# AD9850.net
KiCad netlist of a schematic drawn in Altium Designer
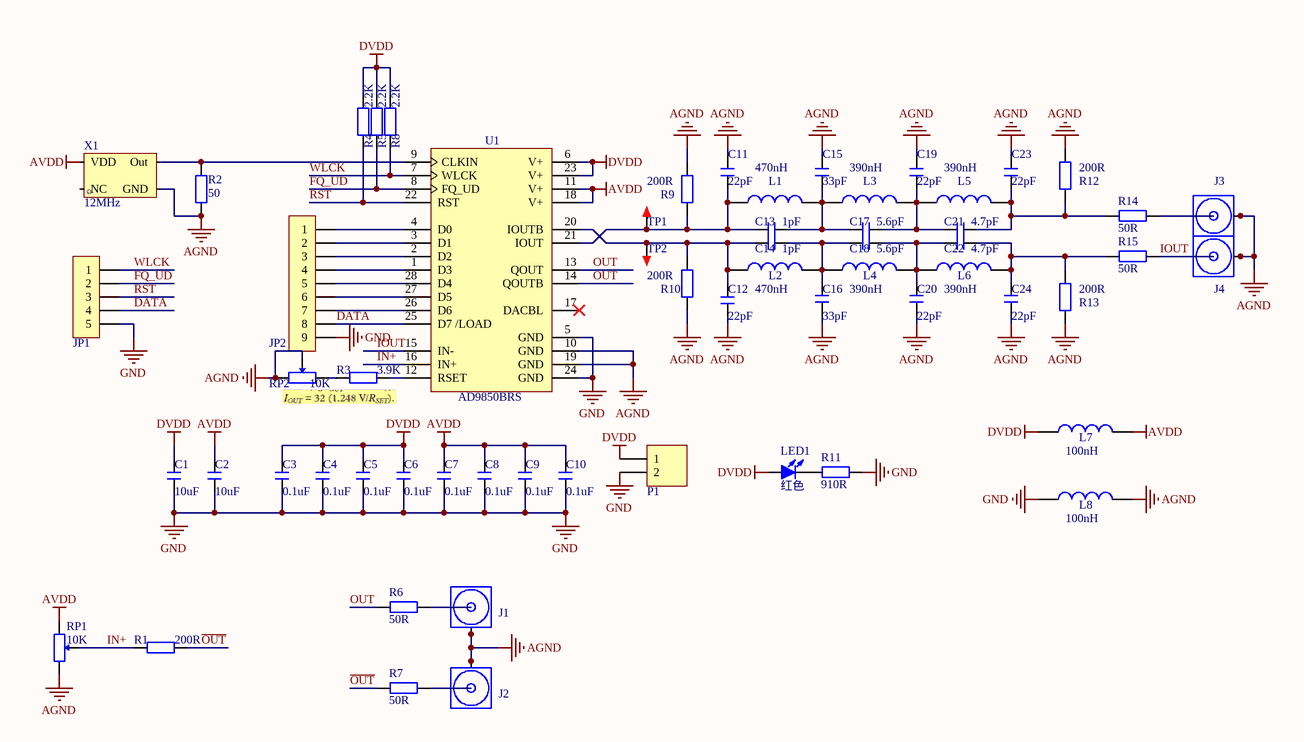
[diagram p0: AD9850模块.SchDoc]

(export (version "E")
  (design (tool "Eeschema 10.0.6"))
  (components
    (comp (ref "C1")
      (value "10uF")
      (footprint "C 0805")
      (description "无极性贴片电容")
      (fields (field (name "版权归属") "源创客"))
      (libsource (lib "电阻-电容-电感") (part "C"))
    )
    (comp (ref "C2")
      (value "10uF")
      (footprint "C 0805")
      (description "无极性贴片电容")
      (fields (field (name "版权归属") "源创客"))
      (libsource (lib "电阻-电容-电感") (part "C"))
    )
    (comp (ref "C3")
      (value "0.1uF")
      (footprint "C 0805")
      (description "无极性贴片电容")
      (fields (field (name "版权归属") "源创客"))
      (libsource (lib "电阻-电容-电感") (part "C"))
    )
    (comp (ref "C4")
      (value "0.1uF")
      (footprint "C 0805")
      (description "无极性贴片电容")
      (fields (field (name "版权归属") "源创客"))
      (libsource (lib "电阻-电容-电感") (part "C"))
    )
    (comp (ref "C5")
      (value "0.1uF")
      (footprint "C 0805")
      (description "无极性贴片电容")
      (fields (field (name "版权归属") "源创客"))
      (libsource (lib "电阻-电容-电感") (part "C"))
    )
    (comp (ref "C6")
      (value "0.1uF")
      (footprint "C 0805")
      (description "无极性贴片电容")
      (fields (field (name "版权归属") "源创客"))
      (libsource (lib "电阻-电容-电感") (part "C"))
    )
    (comp (ref "C7")
      (value "0.1uF")
      (footprint "C 0805")
      (description "无极性贴片电容")
      (fields (field (name "版权归属") "源创客"))
      (libsource (lib "电阻-电容-电感") (part "C"))
    )
    (comp (ref "C8")
      (value "0.1uF")
      (footprint "C 0805")
      (description "无极性贴片电容")
      (fields (field (name "版权归属") "源创客"))
      (libsource (lib "电阻-电容-电感") (part "C"))
    )
    (comp (ref "C9")
      (value "0.1uF")
      (footprint "C 0805")
      (description "无极性贴片电容")
      (fields (field (name "版权归属") "源创客"))
      (libsource (lib "电阻-电容-电感") (part "C"))
    )
    (comp (ref "C10")
      (value "0.1uF")
      (footprint "C 0805")
      (description "无极性贴片电容")
      (fields (field (name "版权归属") "源创客"))
      (libsource (lib "电阻-电容-电感") (part "C"))
    )
    (comp (ref "C11")
      (value "22pF")
      (footprint "C 0603")
      (description "无极性贴片电容")
      (fields (field (name "版权归属") "源创客"))
      (libsource (lib "电阻-电容-电感") (part "C"))
    )
    (comp (ref "C12")
      (value "22pF")
      (footprint "C 0603")
      (description "无极性贴片电容")
      (fields (field (name "版权归属") "源创客"))
      (libsource (lib "电阻-电容-电感") (part "C"))
    )
    (comp (ref "C13")
      (value "1pF")
      (footprint "C 0603")
      (description "无极性贴片电容")
      (fields (field (name "版权归属") "源创客"))
      (libsource (lib "电阻-电容-电感") (part "C"))
    )
    (comp (ref "C14")
      (value "1pF")
      (footprint "C 0603")
      (description "无极性贴片电容")
      (fields (field (name "版权归属") "源创客"))
      (libsource (lib "电阻-电容-电感") (part "C"))
    )
    (comp (ref "C15")
      (value "33pF")
      (footprint "C 0603")
      (description "无极性贴片电容")
      (fields (field (name "版权归属") "源创客"))
      (libsource (lib "电阻-电容-电感") (part "C"))
    )
    (comp (ref "C16")
      (value "33pF")
      (footprint "C 0603")
      (description "无极性贴片电容")
      (fields (field (name "版权归属") "源创客"))
      (libsource (lib "电阻-电容-电感") (part "C"))
    )
    (comp (ref "C17")
      (value "5.6pF")
      (footprint "C 0603")
      (description "无极性贴片电容")
      (fields (field (name "版权归属") "源创客"))
      (libsource (lib "电阻-电容-电感") (part "C"))
    )
    (comp (ref "C18")
      (value "5.6pF")
      (footprint "C 0603")
      (description "无极性贴片电容")
      (fields (field (name "版权归属") "源创客"))
      (libsource (lib "电阻-电容-电感") (part "C"))
    )
    (comp (ref "C19")
      (value "22pF")
      (footprint "C 0603")
      (description "无极性贴片电容")
      (fields (field (name "版权归属") "源创客"))
      (libsource (lib "电阻-电容-电感") (part "C"))
    )
    (comp (ref "C20")
      (value "22pF")
      (footprint "C 0603")
      (description "无极性贴片电容")
      (fields (field (name "版权归属") "源创客"))
      (libsource (lib "电阻-电容-电感") (part "C"))
    )
    (comp (ref "C21")
      (value "4.7pF")
      (footprint "C 0603")
      (description "无极性贴片电容")
      (fields (field (name "版权归属") "源创客"))
      (libsource (lib "电阻-电容-电感") (part "C"))
    )
    (comp (ref "C22")
      (value "4.7pF")
      (footprint "C 0603")
      (description "无极性贴片电容")
      (fields (field (name "版权归属") "源创客"))
      (libsource (lib "电阻-电容-电感") (part "C"))
    )
    (comp (ref "C23")
      (value "22pF")
      (footprint "C 0603")
      (description "无极性贴片电容")
      (fields (field (name "版权归属") "源创客"))
      (libsource (lib "电阻-电容-电感") (part "C"))
    )
    (comp (ref "C24")
      (value "22pF")
      (footprint "C 0603")
      (description "无极性贴片电容")
      (fields (field (name "版权归属") "源创客"))
      (libsource (lib "电阻-电容-电感") (part "C"))
    )
    (comp (ref "J1") (value "COAX") (footprint "MCX5.08-5-H") (libsource (lib "LIB") (part "COAX")))
    (comp (ref "J2") (value "COAX") (footprint "MCX5.08-5-H") (libsource (lib "LIB") (part "COAX")))
    (comp (ref "J3") (value "COAX") (footprint "MCX5.08-5-H") (libsource (lib "LIB") (part "COAX")))
    (comp (ref "J4") (value "COAX") (footprint "MCX5.08-5-H") (libsource (lib "LIB") (part "COAX")))
    (comp (ref "JP1")
      (value "HDR-1X5")
      (footprint "HDR-1X5_H")
      (description "5P接插件")
      (fields (field (name "版权归属") "源创客"))
      (libsource (lib "接插件") (part "Header 5"))
    )
    (comp (ref "JP2")
      (value "HDR-1X9")
      (footprint "HDR-1X9_H")
      (description "9P接插件")
      (fields (field (name "版权归属") "源创客"))
      (libsource (lib "接插件") (part "Header 9"))
    )
    (comp (ref "L1")
      (value "470nH")
      (footprint "L 0603")
      (description "小功率贴片电感")
      (fields (field (name "版权归属") "源创客"))
      (libsource (lib "电阻-电容-电感") (part "L"))
    )
    (comp (ref "L2")
      (value "470nH")
      (footprint "L 0603")
      (description "小功率贴片电感")
      (fields (field (name "版权归属") "源创客"))
      (libsource (lib "电阻-电容-电感") (part "L"))
    )
    (comp (ref "L3")
      (value "390nH")
      (footprint "L 0603")
      (description "小功率贴片电感")
      (fields (field (name "版权归属") "源创客"))
      (libsource (lib "电阻-电容-电感") (part "L"))
    )
    (comp (ref "L4")
      (value "390nH")
      (footprint "L 0603")
      (description "小功率贴片电感")
      (fields (field (name "版权归属") "源创客"))
      (libsource (lib "电阻-电容-电感") (part "L"))
    )
    (comp (ref "L5")
      (value "390nH")
      (footprint "L 0603")
      (description "小功率贴片电感")
      (fields (field (name "版权归属") "源创客"))
      (libsource (lib "电阻-电容-电感") (part "L"))
    )
    (comp (ref "L6")
      (value "390nH")
      (footprint "L 0603")
      (description "小功率贴片电感")
      (fields (field (name "版权归属") "源创客"))
      (libsource (lib "电阻-电容-电感") (part "L"))
    )
    (comp (ref "L7")
      (value "100nH")
      (footprint "L 0603")
      (description "小功率贴片电感")
      (fields (field (name "版权归属") "源创客"))
      (libsource (lib "电阻-电容-电感") (part "L"))
    )
    (comp (ref "L8")
      (value "100nH")
      (footprint "L 0603")
      (description "小功率贴片电感")
      (fields (field (name "版权归属") "源创客"))
      (libsource (lib "电阻-电容-电感") (part "L"))
    )
    (comp (ref "LED1")
      (value "红色")
      (footprint "LED 0805G")
      (description "贴片LED")
      (fields (field (name "版权归属") "源创客"))
      (libsource (lib "LED") (part "LED-SMD"))
    )
    (comp (ref "P1")
      (value "Header 2")
      (footprint "HDR2X1_B2")
      (description "接插件")
      (fields (field (name "PUBLISHER") "Altium Limited"))
      (libsource (lib "LIB") (part "Header 2"))
    )
    (comp (ref "R1")
      (value "200R")
      (footprint "R 0603")
      (description "贴片电阻")
      (fields (field (name "版权归属") "源创客"))
      (libsource (lib "电阻-电容-电感") (part "R"))
    )
    (comp (ref "R2")
      (value "50")
      (footprint "R 0603")
      (description "贴片电阻")
      (fields (field (name "版权归属") "源创客"))
      (libsource (lib "电阻-电容-电感") (part "R"))
    )
    (comp (ref "R3")
      (value "3.9K")
      (footprint "R 0603")
      (description "贴片电阻")
      (fields (field (name "版权归属") "源创客"))
      (libsource (lib "电阻-电容-电感") (part "R"))
    )
    (comp (ref "R4")
      (value "2.2K")
      (footprint "R 0805")
      (description "贴片电阻")
      (fields (field (name "版权归属") "源创客"))
      (libsource (lib "电阻-电容-电感") (part "R"))
    )
    (comp (ref "R5")
      (value "2.2K")
      (footprint "R 0805")
      (description "贴片电阻")
      (fields (field (name "版权归属") "源创客"))
      (libsource (lib "电阻-电容-电感") (part "R"))
    )
    (comp (ref "R6")
      (value "50R")
      (footprint "R 0603")
      (description "贴片电阻")
      (fields (field (name "版权归属") "源创客"))
      (libsource (lib "电阻-电容-电感") (part "R"))
    )
    (comp (ref "R7")
      (value "50R")
      (footprint "R 0603")
      (description "贴片电阻")
      (fields (field (name "版权归属") "源创客"))
      (libsource (lib "电阻-电容-电感") (part "R"))
    )
    (comp (ref "R8")
      (value "2.2K")
      (footprint "R 0805")
      (description "贴片电阻")
      (fields (field (name "版权归属") "源创客"))
      (libsource (lib "电阻-电容-电感") (part "R"))
    )
    (comp (ref "R9")
      (value "200R")
      (footprint "R 0603")
      (description "贴片电阻")
      (fields (field (name "版权归属") "源创客"))
      (libsource (lib "电阻-电容-电感") (part "R"))
    )
    (comp (ref "R10")
      (value "200R")
      (footprint "R 0603")
      (description "贴片电阻")
      (fields (field (name "版权归属") "源创客"))
      (libsource (lib "电阻-电容-电感") (part "R"))
    )
    (comp (ref "R11")
      (value "910R")
      (footprint "R 0805")
      (description "贴片电阻")
      (fields (field (name "版权归属") "源创客"))
      (libsource (lib "电阻-电容-电感") (part "R"))
    )
    (comp (ref "R12")
      (value "200R")
      (footprint "R 0603")
      (description "贴片电阻")
      (fields (field (name "版权归属") "源创客"))
      (libsource (lib "电阻-电容-电感") (part "R"))
    )
    (comp (ref "R13")
      (value "200R")
      (footprint "R 0603")
      (description "贴片电阻")
      (fields (field (name "版权归属") "源创客"))
      (libsource (lib "电阻-电容-电感") (part "R"))
    )
    (comp (ref "R14")
      (value "50R")
      (footprint "R 0603")
      (description "贴片电阻")
      (fields (field (name "版权归属") "源创客"))
      (libsource (lib "电阻-电容-电感") (part "R"))
    )
    (comp (ref "R15")
      (value "50R")
      (footprint "R 0603")
      (description "贴片电阻")
      (fields (field (name "版权归属") "源创客"))
      (libsource (lib "电阻-电容-电感") (part "R"))
    )
    (comp (ref "RP1")
      (value "10K")
      (footprint "3296W")
      (description "插件单联电位器")
      (fields (field (name "版权归属") "源创客"))
      (libsource (lib "电阻-电容-电感") (part "RP-ID"))
    )
    (comp (ref "RP2")
      (value "10K")
      (footprint "3296W")
      (description "插件单联电位器")
      (fields (field (name "版权归属") "源创客"))
      (libsource (lib "电阻-电容-电感") (part "RP-ID"))
    )
    (comp (ref "TP1")
      (value "TEST TP")
      (footprint "TEST TP1.4_B")
      (description "测试环")
      (fields (field (name "版权归属") "源创客"))
      (libsource (lib "未分类器件") (part "TEST TP"))
    )
    (comp (ref "TP2")
      (value "TEST TP")
      (footprint "TEST TP1.4_B")
      (description "测试环")
      (fields (field (name "版权归属") "源创客"))
      (libsource (lib "未分类器件") (part "TEST TP"))
    )
    (comp (ref "U1")
      (value "AD9850BRS")
      (footprint "RS-28")
      (description "CMOS, 125MHz Complete DDS Synthesizer")
      (fields (field (name "PUBLISHER") "Altium Limited"))
      (libsource (lib "AD RF and IF Frequency Synthesiser") (part "AD9850BRS"))
    )
    (comp (ref "X1")
      (value "XTAL")
      (footprint "X-CPX75")
      (description "有源晶振")
      (fields (field (name "FREQUENCY") "12MHz"))
      (libsource (lib "LIB") (part "XTAL_Oscillator"))
    )
  )
  (nets
    (net (code "1") (name "/DATA") (class "Default")
      (node (ref "JP1") (pin "4") (pinfunction "4_4") (pintype "passive"))
      (node (ref "JP2") (pin "8") (pinfunction "8_8") (pintype "passive"))
      (node (ref "U1") (pin "25") (pinfunction "D7_/LOAD_25") (pintype "passive"))
    )
    (net (code "2") (name "/FQ_UD") (class "Default")
      (node (ref "JP1") (pin "2") (pinfunction "2_2") (pintype "passive"))
      (node (ref "R5") (pin "1") (pinfunction "1_1") (pintype "passive"))
      (node (ref "U1") (pin "8") (pinfunction "FQ_UD_8") (pintype "passive"))
    )
    (net (code "3") (name "/IN+") (class "Default")
      (node (ref "R1") (pin "2") (pinfunction "2_2") (pintype "passive"))
      (node (ref "RP1") (pin "2") (pinfunction "2_2") (pintype "passive"))
      (node (ref "U1") (pin "16") (pinfunction "IN+_16") (pintype "passive"))
    )
    (net (code "4") (name "/IOUT") (class "Default")
      (node (ref "J4") (pin "1") (pinfunction "Signal_1") (pintype "passive"))
      (node (ref "R15") (pin "1") (pinfunction "1_1") (pintype "passive"))
      (node (ref "U1") (pin "15") (pinfunction "IN-_15") (pintype "passive"))
    )
    (net (code "5") (name "/OUT") (class "Default")
      (node (ref "R6") (pin "2") (pinfunction "2_2") (pintype "passive"))
      (node (ref "U1") (pin "13") (pinfunction "QOUT_13") (pintype "passive"))
    )
    (net (code "6") (name "/RST") (class "Default")
      (node (ref "JP1") (pin "3") (pinfunction "3_3") (pintype "passive"))
      (node (ref "R4") (pin "1") (pinfunction "1_1") (pintype "passive"))
      (node (ref "U1") (pin "22") (pinfunction "RST_22") (pintype "passive"))
    )
    (net (code "7") (name "/WLCK") (class "Default")
      (node (ref "JP1") (pin "1") (pinfunction "1_1") (pintype "passive"))
      (node (ref "R8") (pin "1") (pinfunction "1_1") (pintype "passive"))
      (node (ref "U1") (pin "7") (pinfunction "WLCK_7") (pintype "passive"))
    )
    (net (code "8") (name "/~{OUT}") (class "Default")
      (node (ref "R1") (pin "1") (pinfunction "1_1") (pintype "passive"))
      (node (ref "R7") (pin "2") (pinfunction "2_2") (pintype "passive"))
      (node (ref "U1") (pin "14") (pinfunction "QOUTB_14") (pintype "passive"))
    )
    (net (code "9") (name "AGND") (class "Default")
      (node (ref "C11") (pin "2") (pinfunction "2_2") (pintype "passive"))
      (node (ref "C12") (pin "2") (pinfunction "2_2") (pintype "passive"))
      (node (ref "C15") (pin "2") (pinfunction "2_2") (pintype "passive"))
      (node (ref "C16") (pin "2") (pinfunction "2_2") (pintype "passive"))
      (node (ref "C19") (pin "2") (pinfunction "2_2") (pintype "passive"))
      (node (ref "C20") (pin "2") (pinfunction "2_2") (pintype "passive"))
      (node (ref "C23") (pin "2") (pinfunction "2_2") (pintype "passive"))
      (node (ref "C24") (pin "2") (pinfunction "2_2") (pintype "passive"))
      (node (ref "J1") (pin "2") (pinfunction "GND_2") (pintype "passive"))
      (node (ref "J1") (pin "3") (pinfunction "GND_3") (pintype "passive"))
      (node (ref "J1") (pin "4") (pinfunction "GND_4") (pintype "passive"))
      (node (ref "J1") (pin "5") (pinfunction "GND_5") (pintype "passive"))
      (node (ref "J2") (pin "2") (pinfunction "GND_2") (pintype "passive"))
      (node (ref "J2") (pin "3") (pinfunction "GND_3") (pintype "passive"))
      (node (ref "J2") (pin "4") (pinfunction "GND_4") (pintype "passive"))
      (node (ref "J2") (pin "5") (pinfunction "GND_5") (pintype "passive"))
      (node (ref "J3") (pin "2") (pinfunction "GND_2") (pintype "passive"))
      (node (ref "J3") (pin "3") (pinfunction "GND_3") (pintype "passive"))
      (node (ref "J3") (pin "4") (pinfunction "GND_4") (pintype "passive"))
      (node (ref "J3") (pin "5") (pinfunction "GND_5") (pintype "passive"))
      (node (ref "J4") (pin "2") (pinfunction "GND_2") (pintype "passive"))
      (node (ref "J4") (pin "3") (pinfunction "GND_3") (pintype "passive"))
      (node (ref "J4") (pin "4") (pinfunction "GND_4") (pintype "passive"))
      (node (ref "J4") (pin "5") (pinfunction "GND_5") (pintype "passive"))
      (node (ref "L8") (pin "2") (pinfunction "2_2") (pintype "passive"))
      (node (ref "R10") (pin "1") (pinfunction "1_1") (pintype "passive"))
      (node (ref "R12") (pin "2") (pinfunction "2_2") (pintype "passive"))
      (node (ref "R13") (pin "1") (pinfunction "1_1") (pintype "passive"))
      (node (ref "R2") (pin "1") (pinfunction "1_1") (pintype "passive"))
      (node (ref "R9") (pin "2") (pinfunction "2_2") (pintype "passive"))
      (node (ref "RP1") (pin "3") (pinfunction "3_3") (pintype "passive"))
      (node (ref "RP2") (pin "1") (pinfunction "1_1") (pintype "passive"))
      (node (ref "RP2") (pin "2") (pinfunction "2_2") (pintype "passive"))
      (node (ref "U1") (pin "10") (pinfunction "GND_10") (pintype "power_in"))
      (node (ref "U1") (pin "19") (pinfunction "GND_19") (pintype "power_in"))
      (node (ref "X1") (pin "2") (pinfunction "GND_2") (pintype "passive"))
    )
    (net (code "10") (name "AVDD") (class "Default")
      (node (ref "C10") (pin "2") (pinfunction "2_2") (pintype "passive"))
      (node (ref "C2") (pin "2") (pinfunction "2_2") (pintype "passive"))
      (node (ref "C7") (pin "2") (pinfunction "2_2") (pintype "passive"))
      (node (ref "C8") (pin "2") (pinfunction "2_2") (pintype "passive"))
      (node (ref "C9") (pin "2") (pinfunction "2_2") (pintype "passive"))
      (node (ref "L7") (pin "2") (pinfunction "2_2") (pintype "passive"))
      (node (ref "RP1") (pin "1") (pinfunction "1_1") (pintype "passive"))
      (node (ref "U1") (pin "11") (pinfunction "V+_11") (pintype "power_in"))
      (node (ref "U1") (pin "18") (pinfunction "V+_18") (pintype "power_in"))
      (node (ref "X1") (pin "4") (pinfunction "VDD_4") (pintype "passive"))
    )
    (net (code "11") (name "DVDD") (class "Default")
      (node (ref "C1") (pin "2") (pinfunction "2_2") (pintype "passive"))
      (node (ref "C3") (pin "2") (pinfunction "2_2") (pintype "passive"))
      (node (ref "C4") (pin "2") (pinfunction "2_2") (pintype "passive"))
      (node (ref "C5") (pin "2") (pinfunction "2_2") (pintype "passive"))
      (node (ref "C6") (pin "2") (pinfunction "2_2") (pintype "passive"))
      (node (ref "L7") (pin "1") (pinfunction "1_1") (pintype "passive"))
      (node (ref "LED1") (pin "1") (pinfunction "A_1") (pintype "passive"))
      (node (ref "P1") (pin "1") (pinfunction "1_1") (pintype "passive"))
      (node (ref "R4") (pin "2") (pinfunction "2_2") (pintype "passive"))
      (node (ref "R5") (pin "2") (pinfunction "2_2") (pintype "passive"))
      (node (ref "R8") (pin "2") (pinfunction "2_2") (pintype "passive"))
      (node (ref "U1") (pin "23") (pinfunction "V+_23") (pintype "power_in"))
      (node (ref "U1") (pin "6") (pinfunction "V+_6") (pintype "power_in"))
    )
    (net (code "12") (name "GND") (class "Default")
      (node (ref "C1") (pin "1") (pinfunction "1_1") (pintype "passive"))
      (node (ref "C10") (pin "1") (pinfunction "1_1") (pintype "passive"))
      (node (ref "C2") (pin "1") (pinfunction "1_1") (pintype "passive"))
      (node (ref "C3") (pin "1") (pinfunction "1_1") (pintype "passive"))
      (node (ref "C4") (pin "1") (pinfunction "1_1") (pintype "passive"))
      (node (ref "C5") (pin "1") (pinfunction "1_1") (pintype "passive"))
      (node (ref "C6") (pin "1") (pinfunction "1_1") (pintype "passive"))
      (node (ref "C7") (pin "1") (pinfunction "1_1") (pintype "passive"))
      (node (ref "C8") (pin "1") (pinfunction "1_1") (pintype "passive"))
      (node (ref "C9") (pin "1") (pinfunction "1_1") (pintype "passive"))
      (node (ref "JP1") (pin "5") (pinfunction "5_5") (pintype "passive"))
      (node (ref "JP2") (pin "9") (pinfunction "9_9") (pintype "passive"))
      (node (ref "L8") (pin "1") (pinfunction "1_1") (pintype "passive"))
      (node (ref "P1") (pin "2") (pinfunction "2_2") (pintype "passive"))
      (node (ref "R11") (pin "1") (pinfunction "1_1") (pintype "passive"))
      (node (ref "U1") (pin "24") (pinfunction "GND_24") (pintype "power_in"))
      (node (ref "U1") (pin "5") (pinfunction "GND_5") (pintype "power_in"))
    )
    (net (code "13") (name "Net-(C13-Pad2)") (class "Default")
      (node (ref "C13") (pin "2") (pinfunction "2_2") (pintype "passive"))
      (node (ref "C15") (pin "1") (pinfunction "1_1") (pintype "passive"))
      (node (ref "C17") (pin "1") (pinfunction "1_1") (pintype "passive"))
      (node (ref "L1") (pin "2") (pinfunction "2_2") (pintype "passive"))
      (node (ref "L3") (pin "1") (pinfunction "1_1") (pintype "passive"))
    )
    (net (code "14") (name "Net-(C14-Pad1)") (class "Default")
      (node (ref "C14") (pin "1") (pinfunction "1_1") (pintype "passive"))
      (node (ref "C16") (pin "1") (pinfunction "1_1") (pintype "passive"))
      (node (ref "C18") (pin "2") (pinfunction "2_2") (pintype "passive"))
      (node (ref "L2") (pin "2") (pinfunction "2_2") (pintype "passive"))
      (node (ref "L4") (pin "1") (pinfunction "1_1") (pintype "passive"))
    )
    (net (code "15") (name "Net-(C17-Pad2)") (class "Default")
      (node (ref "C17") (pin "2") (pinfunction "2_2") (pintype "passive"))
      (node (ref "C19") (pin "1") (pinfunction "1_1") (pintype "passive"))
      (node (ref "C21") (pin "1") (pinfunction "1_1") (pintype "passive"))
      (node (ref "L3") (pin "2") (pinfunction "2_2") (pintype "passive"))
      (node (ref "L5") (pin "1") (pinfunction "1_1") (pintype "passive"))
    )
    (net (code "16") (name "Net-(C18-Pad1)") (class "Default")
      (node (ref "C18") (pin "1") (pinfunction "1_1") (pintype "passive"))
      (node (ref "C20") (pin "1") (pinfunction "1_1") (pintype "passive"))
      (node (ref "C22") (pin "2") (pinfunction "2_2") (pintype "passive"))
      (node (ref "L4") (pin "2") (pinfunction "2_2") (pintype "passive"))
      (node (ref "L6") (pin "1") (pinfunction "1_1") (pintype "passive"))
    )
    (net (code "17") (name "Net-(C21-Pad2)") (class "Default")
      (node (ref "C21") (pin "2") (pinfunction "2_2") (pintype "passive"))
      (node (ref "C23") (pin "1") (pinfunction "1_1") (pintype "passive"))
      (node (ref "L5") (pin "2") (pinfunction "2_2") (pintype "passive"))
      (node (ref "R12") (pin "1") (pinfunction "1_1") (pintype "passive"))
      (node (ref "R14") (pin "2") (pinfunction "2_2") (pintype "passive"))
    )
    (net (code "18") (name "Net-(C22-Pad1)") (class "Default")
      (node (ref "C22") (pin "1") (pinfunction "1_1") (pintype "passive"))
      (node (ref "C24") (pin "1") (pinfunction "1_1") (pintype "passive"))
      (node (ref "L6") (pin "2") (pinfunction "2_2") (pintype "passive"))
      (node (ref "R13") (pin "2") (pinfunction "2_2") (pintype "passive"))
      (node (ref "R15") (pin "2") (pinfunction "2_2") (pintype "passive"))
    )
    (net (code "19") (name "Net-(J1-Signal)") (class "Default")
      (node (ref "J1") (pin "1") (pinfunction "Signal_1") (pintype "passive"))
      (node (ref "R6") (pin "1") (pinfunction "1_1") (pintype "passive"))
    )
    (net (code "20") (name "Net-(J2-Signal)") (class "Default")
      (node (ref "J2") (pin "1") (pinfunction "Signal_1") (pintype "passive"))
      (node (ref "R7") (pin "1") (pinfunction "1_1") (pintype "passive"))
    )
    (net (code "21") (name "Net-(J3-Signal)") (class "Default")
      (node (ref "J3") (pin "1") (pinfunction "Signal_1") (pintype "passive"))
      (node (ref "R14") (pin "1") (pinfunction "1_1") (pintype "passive"))
    )
    (net (code "22") (name "Net-(LED1-K)") (class "Default")
      (node (ref "LED1") (pin "2") (pinfunction "K_2") (pintype "passive"))
      (node (ref "R11") (pin "2") (pinfunction "2_2") (pintype "passive"))
    )
    (net (code "23") (name "Net-(R3-Pad1)") (class "Default")
      (node (ref "R3") (pin "1") (pinfunction "1_1") (pintype "passive"))
      (node (ref "RP2") (pin "3") (pinfunction "3_3") (pintype "passive"))
    )
    (net (code "24") (name "Net-(U1-CLKIN)") (class "Default")
      (node (ref "R2") (pin "2") (pinfunction "2_2") (pintype "passive"))
      (node (ref "U1") (pin "9") (pinfunction "CLKIN_9") (pintype "passive"))
      (node (ref "X1") (pin "3") (pinfunction "Out_3") (pintype "passive"))
    )
    (net (code "25") (name "Net-(U1-D0)") (class "Default")
      (node (ref "JP2") (pin "1") (pinfunction "1_1") (pintype "passive"))
      (node (ref "U1") (pin "4") (pinfunction "D0_4") (pintype "passive"))
    )
    (net (code "26") (name "Net-(U1-D1)") (class "Default")
      (node (ref "JP2") (pin "2") (pinfunction "2_2") (pintype "passive"))
      (node (ref "U1") (pin "3") (pinfunction "D1_3") (pintype "passive"))
    )
    (net (code "27") (name "Net-(U1-D2)") (class "Default")
      (node (ref "JP2") (pin "3") (pinfunction "3_3") (pintype "passive"))
      (node (ref "U1") (pin "2") (pinfunction "D2_2") (pintype "passive"))
    )
    (net (code "28") (name "Net-(U1-D3)") (class "Default")
      (node (ref "JP2") (pin "4") (pinfunction "4_4") (pintype "passive"))
      (node (ref "U1") (pin "1") (pinfunction "D3_1") (pintype "open_collector"))
    )
    (net (code "29") (name "Net-(U1-D4)") (class "Default")
      (node (ref "JP2") (pin "5") (pinfunction "5_5") (pintype "passive"))
      (node (ref "U1") (pin "28") (pinfunction "D4_28") (pintype "passive"))
    )
    (net (code "30") (name "Net-(U1-D5)") (class "Default")
      (node (ref "JP2") (pin "6") (pinfunction "6_6") (pintype "passive"))
      (node (ref "U1") (pin "27") (pinfunction "D5_27") (pintype "passive"))
    )
    (net (code "31") (name "Net-(U1-D6)") (class "Default")
      (node (ref "JP2") (pin "7") (pinfunction "7_7") (pintype "passive"))
      (node (ref "U1") (pin "26") (pinfunction "D6_26") (pintype "passive"))
    )
    (net (code "32") (name "Net-(U1-IOUT)") (class "Default")
      (node (ref "C11") (pin "1") (pinfunction "1_1") (pintype "passive"))
      (node (ref "C13") (pin "1") (pinfunction "1_1") (pintype "passive"))
      (node (ref "L1") (pin "1") (pinfunction "1_1") (pintype "passive"))
      (node (ref "R9") (pin "1") (pinfunction "1_1") (pintype "passive"))
      (node (ref "TP1") (pin "1") (pinfunction "1_1") (pintype "passive"))
      (node (ref "U1") (pin "21") (pinfunction "IOUT_21") (pintype "passive"))
    )
    (net (code "33") (name "Net-(U1-IOUTB)") (class "Default")
      (node (ref "C12") (pin "1") (pinfunction "1_1") (pintype "passive"))
      (node (ref "C14") (pin "2") (pinfunction "2_2") (pintype "passive"))
      (node (ref "L2") (pin "1") (pinfunction "1_1") (pintype "passive"))
      (node (ref "R10") (pin "2") (pinfunction "2_2") (pintype "passive"))
      (node (ref "TP2") (pin "1") (pinfunction "1_1") (pintype "passive"))
      (node (ref "U1") (pin "20") (pinfunction "IOUTB_20") (pintype "passive"))
    )
    (net (code "34") (name "Net-(U1-RSET)") (class "Default")
      (node (ref "R3") (pin "2") (pinfunction "2_2") (pintype "passive"))
      (node (ref "U1") (pin "12") (pinfunction "RSET_12") (pintype "passive"))
    )
    (net (code "35") (name "unconnected-(U1-DACBL-Pad17)") (class "Default")
      (node (ref "U1") (pin "17") (pinfunction "DACBL_17") (pintype "passive+no_connect"))
    )
    (net (code "36") (name "unconnected-(X1-NC-Pad1)") (class "Default")
      (node (ref "X1") (pin "1") (pinfunction "NC_1") (pintype "passive"))
    )
  )
)
